# data_interface.net
KiCad netlist of a schematic drawn in Altium Designer
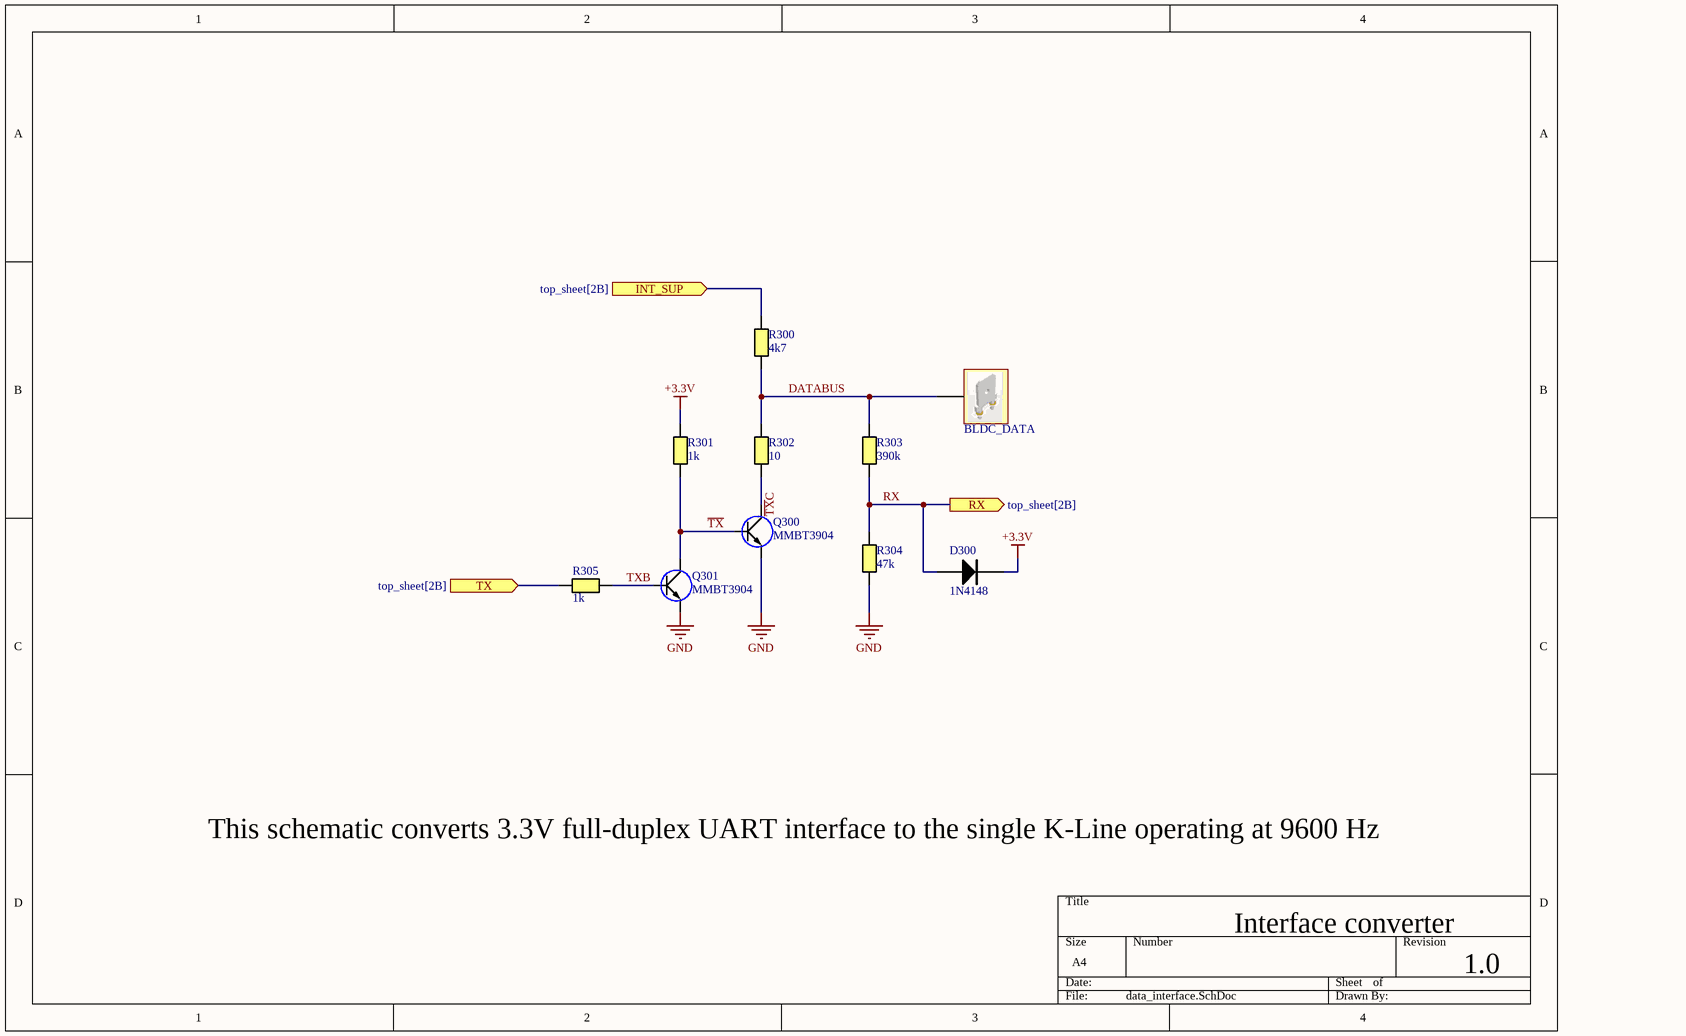
[diagram p0: data_interface.SchDoc]

(export (version "E")
  (design (tool "Eeschema 10.0.6"))
  (components
    (comp (ref "BLDC_DATA")
      (value "Crimp 6.3 single PCB")
      (footprint "Crimp 6.3mm single PCB")
      (description "Straight Mount Angle PCB Tab Terminal")
      (libsource (lib "Connectors") (part "Crimp 6.3 single PCB"))
    )
    (comp (ref "D300")
      (value "1N4148")
      (footprint "SOD80")
      (description "Small Signal Fast Switching Diodes")
      (libsource (lib "Diodes") (part "1N4148"))
    )
    (comp (ref "Q300")
      (value "MMBT3904")
      (footprint "SOT23")
      (description "NPN General Purpose Transistor")
      (libsource (lib "Transistors") (part "2N3904"))
    )
    (comp (ref "Q301")
      (value "MMBT3904")
      (footprint "SOT23")
      (description "NPN General Purpose Transistor")
      (libsource (lib "Transistors") (part "2N3904"))
    )
    (comp (ref "R300")
      (value "4k7")
      (footprint "RESC0603(1608)_N")
      (description "Resistor Medium Density")
      (libsource (lib "") (part "Resistor M_1"))
    )
    (comp (ref "R301")
      (value "1k")
      (footprint "RESC0603(1608)_N")
      (description "Resistor Medium Density")
      (libsource (lib "") (part "Resistor M_1"))
    )
    (comp (ref "R302")
      (value "10")
      (footprint "RESC0603(1608)_N")
      (description "Resistor Medium Density")
      (libsource (lib "") (part "Resistor M_1"))
    )
    (comp (ref "R303")
      (value "390k")
      (footprint "RESC0603(1608)_N")
      (description "Resistor Medium Density")
      (libsource (lib "") (part "Resistor M_1"))
    )
    (comp (ref "R304")
      (value "47k")
      (footprint "RESC0603(1608)_N")
      (description "Resistor Medium Density")
      (libsource (lib "") (part "Resistor M_1"))
    )
    (comp (ref "R305")
      (value "1k")
      (footprint "RESC0603(1608)_N")
      (description "Resistor Medium Density")
      (libsource (lib "Discrete") (part "Resistor M"))
    )
  )
  (nets
    (net (code "1") (name "+3.3V") (class "Default")
      (node (ref "D300") (pin "2") (pinfunction "K_2") (pintype "passive"))
      (node (ref "R301") (pin "2") (pinfunction "2_2") (pintype "passive"))
    )
    (net (code "2") (name "/DATABUS") (class "Default")
      (node (ref "BLDC_DATA") (pin "1") (pintype "passive"))
      (node (ref "R300") (pin "1") (pinfunction "1_1") (pintype "passive"))
      (node (ref "R302") (pin "2") (pinfunction "2_2") (pintype "passive"))
      (node (ref "R303") (pin "2") (pinfunction "2_2") (pintype "passive"))
    )
    (net (code "3") (name "/INT_SUP") (class "Default")
      (node (ref "R300") (pin "2") (pinfunction "2_2") (pintype "passive"))
    )
    (net (code "4") (name "/RX") (class "Default")
      (node (ref "D300") (pin "1") (pinfunction "A_1") (pintype "passive"))
      (node (ref "R303") (pin "1") (pinfunction "1_1") (pintype "passive"))
      (node (ref "R304") (pin "2") (pinfunction "2_2") (pintype "passive"))
    )
    (net (code "5") (name "/TX") (class "Default")
      (node (ref "R305") (pin "1") (pinfunction "1_1") (pintype "passive"))
    )
    (net (code "6") (name "/TXB") (class "Default")
      (node (ref "Q301") (pin "1") (pinfunction "B_1") (pintype "passive"))
      (node (ref "R305") (pin "2") (pinfunction "2_2") (pintype "passive"))
    )
    (net (code "7") (name "/~{TX}") (class "Default")
      (node (ref "Q300") (pin "1") (pinfunction "B_1") (pintype "passive"))
      (node (ref "Q301") (pin "3") (pinfunction "C_3") (pintype "passive"))
      (node (ref "R301") (pin "1") (pinfunction "1_1") (pintype "passive"))
    )
    (net (code "8") (name "/~{TX}C") (class "Default")
      (node (ref "Q300") (pin "3") (pinfunction "C_3") (pintype "passive"))
      (node (ref "R302") (pin "1") (pinfunction "1_1") (pintype "passive"))
    )
    (net (code "9") (name "GND") (class "Default")
      (node (ref "Q300") (pin "2") (pinfunction "E_2") (pintype "passive"))
      (node (ref "Q301") (pin "2") (pinfunction "E_2") (pintype "passive"))
      (node (ref "R304") (pin "1") (pinfunction "1_1") (pintype "passive"))
    )
  )
)
